# Sheet1.net
KiCad netlist of a schematic drawn in Altium Designer
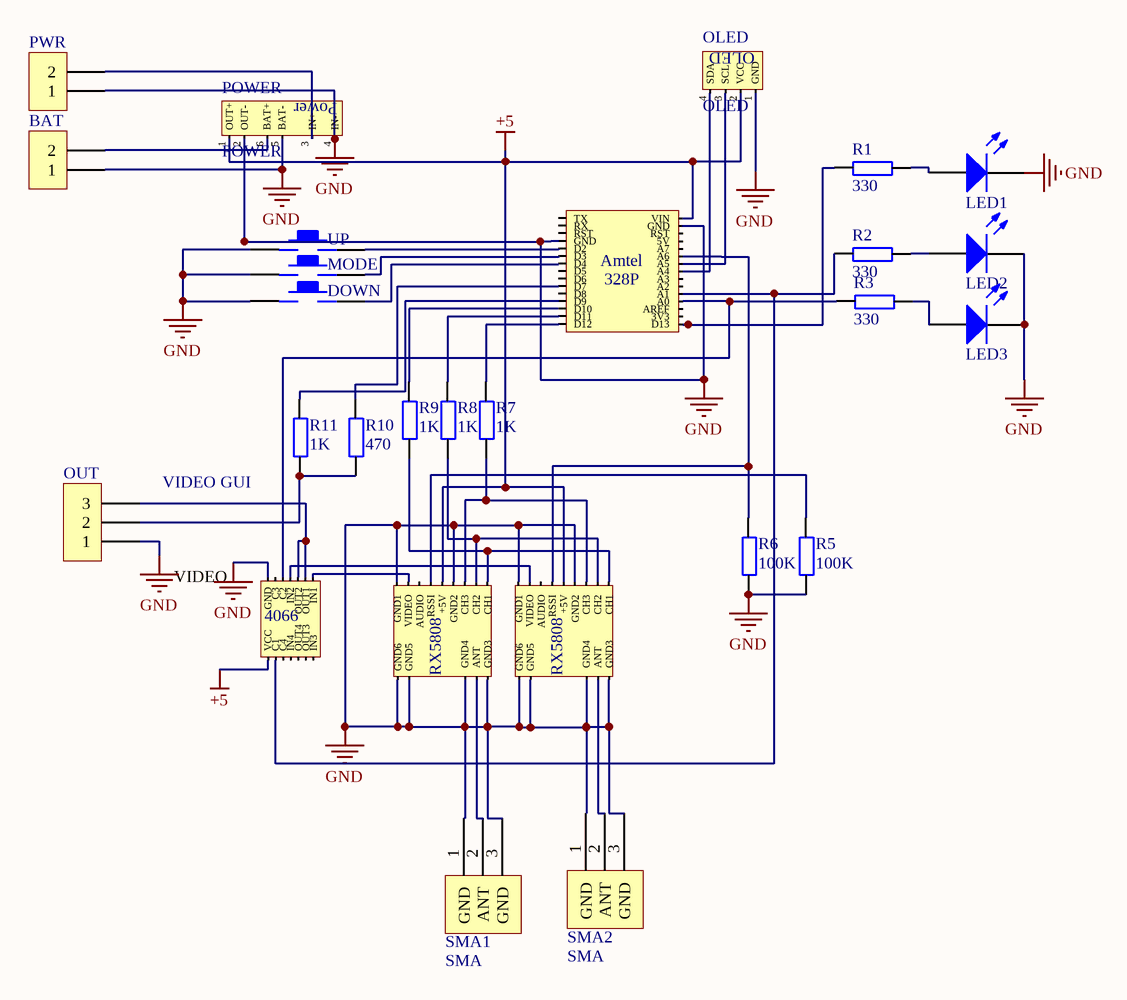
[diagram p0: Sheet1.SchDoc]

(export (version "E")
  (design (tool "Eeschema 10.0.6"))
  (components
    (comp (ref "AT328P") (value "328P") (footprint "328") (libsource (lib "328P") (part "328P")))
    (comp (ref "BAT") (value "CON2") (footprint "SIP2") (libsource (lib "常用元件库") (part "CON2")))
    (comp (ref "CD4066") (value "CD4066") (footprint "4066") (libsource (lib "CD4066") (part "CD4066")))
    (comp (ref "DS1")
      (value "LED1")
      (footprint "1206")
      (description "Typical RED, GREEN, YELLOW, AMBER GaAs LED")
      (fields (field (name "PUBLISHER") "Altium Limited"))
      (libsource (lib "MiniSTM32 V3.0封装库") (part "LED2"))
    )
    (comp (ref "DS2")
      (value "LED2")
      (footprint "1206")
      (description "Typical RED, GREEN, YELLOW, AMBER GaAs LED")
      (fields (field (name "PUBLISHER") "Altium Limited"))
      (libsource (lib "MiniSTM32 V3.0封装库") (part "LED2"))
    )
    (comp (ref "DS3")
      (value "LED3")
      (footprint "1206")
      (description "Typical RED, GREEN, YELLOW, AMBER GaAs LED")
      (fields (field (name "PUBLISHER") "Altium Limited"))
      (libsource (lib "MiniSTM32 V3.0封装库") (part "LED2"))
    )
    (comp (ref "KEY1") (value "UP") (footprint "KEY_M") (libsource (lib "MiniSTM32 V3.0封装库") (part "KEY_M")))
    (comp (ref "KEY2")
      (value "MODE")
      (footprint "KEY_M")
      (libsource (lib "MiniSTM32 V3.0封装库") (part "KEY_M"))
    )
    (comp (ref "KEY3")
      (value "DOWN")
      (footprint "KEY_M")
      (libsource (lib "MiniSTM32 V3.0封装库") (part "KEY_M"))
    )
    (comp (ref "OLED") (value "OLED") (footprint "oled") (libsource (lib "OLED") (part "OLED")))
    (comp (ref "OUT") (value "CON3") (footprint "SIP3") (libsource (lib "常用元件库") (part "CON3")))
    (comp (ref "POWER") (value "POWER") (footprint "power") (libsource (lib "POWER") (part "POWER")))
    (comp (ref "PWR") (value "CON1") (footprint "SIP2") (libsource (lib "常用元件库") (part "CON2")))
    (comp (ref "R1") (value "330") (footprint "0805") (libsource (lib "MiniSTM32 V3.0封装库") (part "R")))
    (comp (ref "R2") (value "330") (footprint "0805") (libsource (lib "MiniSTM32 V3.0封装库") (part "R")))
    (comp (ref "R3") (value "330") (footprint "0805") (libsource (lib "MiniSTM32 V3.0封装库") (part "R")))
    (comp (ref "R5") (value "100K") (footprint "0805") (libsource (lib "MiniSTM32 V3.0封装库") (part "R")))
    (comp (ref "R6") (value "100K") (footprint "0805") (libsource (lib "MiniSTM32 V3.0封装库") (part "R")))
    (comp (ref "R7") (value "1K") (footprint "0805") (libsource (lib "MiniSTM32 V3.0封装库") (part "R")))
    (comp (ref "R8") (value "1K") (footprint "0805") (libsource (lib "MiniSTM32 V3.0封装库") (part "R")))
    (comp (ref "R9") (value "1K") (footprint "0805") (libsource (lib "MiniSTM32 V3.0封装库") (part "R")))
    (comp (ref "R10") (value "470") (footprint "0805") (libsource (lib "MiniSTM32 V3.0封装库") (part "R")))
    (comp (ref "R11") (value "1K") (footprint "0805") (libsource (lib "MiniSTM32 V3.0封装库") (part "R")))
    (comp (ref "RX5808 1") (value "RX5808") (footprint "rx5808") (libsource (lib "RX5808") (part "RX5808")))
    (comp (ref "RX5808 2") (value "RX5808") (footprint "rx5808") (libsource (lib "RX5808") (part "RX5808")))
    (comp (ref "SMA1") (value "SMA") (footprint "SMA") (libsource (lib "SMA") (part "Component_1")))
    (comp (ref "SMA2") (value "SMA") (footprint "SMA") (libsource (lib "SMA") (part "Component_1")))
  )
  (nets
    (net (code "1") (name "+5") (class "Default")
      (node (ref "AT328P") (pin "30") (pinfunction "VIN_30") (pintype "passive"))
      (node (ref "CD4066") (pin "14") (pinfunction "VCC_14") (pintype "passive"))
      (node (ref "OLED") (pin "2") (pinfunction "VCC_2") (pintype "passive"))
      (node (ref "POWER") (pin "1") (pinfunction "OUT+_1") (pintype "passive"))
      (node (ref "RX5808 1") (pin "5") (pinfunction "+5V_5") (pintype "passive"))
      (node (ref "RX5808 2") (pin "5") (pinfunction "+5V_5") (pintype "passive"))
    )
    (net (code "2") (name "GND") (class "Default")
      (node (ref "AT328P") (pin "29") (pinfunction "GND_29") (pintype "passive"))
      (node (ref "AT328P") (pin "4") (pinfunction "GND_4") (pintype "passive"))
      (node (ref "BAT") (pin "1") (pinfunction "1_1") (pintype "passive"))
      (node (ref "CD4066") (pin "7") (pinfunction "GND_7") (pintype "passive"))
      (node (ref "DS1") (pin "2") (pinfunction "K_2") (pintype "passive"))
      (node (ref "DS2") (pin "2") (pinfunction "K_2") (pintype "passive"))
      (node (ref "DS3") (pin "2") (pinfunction "K_2") (pintype "passive"))
      (node (ref "KEY1") (pin "1") (pinfunction "1_1") (pintype "passive"))
      (node (ref "KEY2") (pin "1") (pinfunction "1_1") (pintype "passive"))
      (node (ref "KEY3") (pin "1") (pinfunction "1_1") (pintype "passive"))
      (node (ref "OLED") (pin "1") (pinfunction "GND_1") (pintype "passive"))
      (node (ref "OUT") (pin "1") (pinfunction "1_1") (pintype "passive"))
      (node (ref "POWER") (pin "2") (pinfunction "OUT-_2") (pintype "passive"))
      (node (ref "POWER") (pin "4") (pinfunction "IN-_4") (pintype "passive"))
      (node (ref "POWER") (pin "5") (pinfunction "BAT-_5") (pintype "passive"))
      (node (ref "PWR") (pin "1") (pinfunction "1_1") (pintype "passive"))
      (node (ref "R5") (pin "1") (pintype "passive"))
      (node (ref "R6") (pin "1") (pintype "passive"))
      (node (ref "RX5808 1") (pin "10") (pinfunction "GND3_10") (pintype "passive"))
      (node (ref "RX5808 1") (pin "12") (pinfunction "GND4_12") (pintype "passive"))
      (node (ref "RX5808 1") (pin "13") (pinfunction "GND5_13") (pintype "passive"))
      (node (ref "RX5808 1") (pin "14") (pinfunction "GND6_14") (pintype "passive"))
      (node (ref "RX5808 1") (pin "4") (pinfunction "GND2_4") (pintype "passive"))
      (node (ref "RX5808 1") (pin "9") (pinfunction "GND1_9") (pintype "passive"))
      (node (ref "RX5808 2") (pin "10") (pinfunction "GND3_10") (pintype "passive"))
      (node (ref "RX5808 2") (pin "12") (pinfunction "GND4_12") (pintype "passive"))
      (node (ref "RX5808 2") (pin "13") (pinfunction "GND5_13") (pintype "passive"))
      (node (ref "RX5808 2") (pin "14") (pinfunction "GND6_14") (pintype "passive"))
      (node (ref "RX5808 2") (pin "4") (pinfunction "GND2_4") (pintype "passive"))
      (node (ref "RX5808 2") (pin "9") (pinfunction "GND1_9") (pintype "passive"))
      (node (ref "SMA1") (pin "1") (pinfunction "GND_1") (pintype "passive"))
      (node (ref "SMA1") (pin "3") (pinfunction "GND_3") (pintype "passive"))
      (node (ref "SMA2") (pin "1") (pinfunction "GND_1") (pintype "passive"))
      (node (ref "SMA2") (pin "3") (pinfunction "GND_3") (pintype "passive"))
    )
    (net (code "3") (name "Net-(AT328P-A0)") (class "Default")
      (node (ref "AT328P") (pin "19") (pinfunction "A0_19") (pintype "passive"))
      (node (ref "CD4066") (pin "5") (pinfunction "C2_5") (pintype "passive"))
      (node (ref "R3") (pin "1") (pintype "passive"))
    )
    (net (code "4") (name "Net-(AT328P-A1)") (class "Default")
      (node (ref "AT328P") (pin "20") (pinfunction "A1_20") (pintype "passive"))
      (node (ref "CD4066") (pin "13") (pinfunction "C1_13") (pintype "passive"))
      (node (ref "R2") (pin "1") (pintype "passive"))
    )
    (net (code "5") (name "Net-(AT328P-A4)") (class "Default")
      (node (ref "AT328P") (pin "23") (pinfunction "A4_23") (pintype "passive"))
      (node (ref "OLED") (pin "4") (pinfunction "SDA_4") (pintype "passive"))
    )
    (net (code "6") (name "Net-(AT328P-A5)") (class "Default")
      (node (ref "AT328P") (pin "24") (pinfunction "A5_24") (pintype "passive"))
      (node (ref "OLED") (pin "3") (pinfunction "SCL_3") (pintype "passive"))
    )
    (net (code "7") (name "Net-(AT328P-A6)") (class "Default")
      (node (ref "AT328P") (pin "25") (pinfunction "A6_25") (pintype "passive"))
      (node (ref "R6") (pin "2") (pintype "passive"))
      (node (ref "RX5808 2") (pin "6") (pinfunction "RSSI_6") (pintype "passive"))
    )
    (net (code "8") (name "Net-(AT328P-D2)") (class "Default")
      (node (ref "AT328P") (pin "5") (pinfunction "D2_5") (pintype "passive"))
      (node (ref "KEY1") (pin "2") (pinfunction "2_2") (pintype "passive"))
    )
    (net (code "9") (name "Net-(AT328P-D3)") (class "Default")
      (node (ref "AT328P") (pin "6") (pinfunction "D3_6") (pintype "passive"))
      (node (ref "KEY2") (pin "2") (pinfunction "2_2") (pintype "passive"))
    )
    (net (code "10") (name "Net-(AT328P-D4)") (class "Default")
      (node (ref "AT328P") (pin "7") (pinfunction "D4_7") (pintype "passive"))
      (node (ref "KEY3") (pin "2") (pinfunction "2_2") (pintype "passive"))
    )
    (net (code "11") (name "Net-(AT328P-D7)") (class "Default")
      (node (ref "AT328P") (pin "10") (pinfunction "D7_10") (pintype "passive"))
      (node (ref "R10") (pin "2") (pintype "passive"))
    )
    (net (code "12") (name "Net-(AT328P-D9)") (class "Default")
      (node (ref "AT328P") (pin "12") (pinfunction "D9_12") (pintype "passive"))
      (node (ref "R11") (pin "2") (pintype "passive"))
    )
    (net (code "13") (name "Net-(AT328P-D10)") (class "Default")
      (node (ref "AT328P") (pin "13") (pinfunction "D10_13") (pintype "passive"))
      (node (ref "R9") (pin "2") (pintype "passive"))
    )
    (net (code "14") (name "Net-(AT328P-D11)") (class "Default")
      (node (ref "AT328P") (pin "14") (pinfunction "D11_14") (pintype "passive"))
      (node (ref "R8") (pin "2") (pintype "passive"))
    )
    (net (code "15") (name "Net-(AT328P-D12)") (class "Default")
      (node (ref "AT328P") (pin "15") (pinfunction "D12_15") (pintype "passive"))
      (node (ref "R7") (pin "2") (pintype "passive"))
    )
    (net (code "16") (name "Net-(AT328P-D13)") (class "Default")
      (node (ref "AT328P") (pin "16") (pinfunction "D13_16") (pintype "passive"))
      (node (ref "R1") (pin "1") (pintype "passive"))
    )
    (net (code "17") (name "Net-(CD4066-IN1)") (class "Default")
      (node (ref "CD4066") (pin "1") (pinfunction "IN1_1") (pintype "passive"))
      (node (ref "RX5808 1") (pin "8") (pinfunction "VIDEO_8") (pintype "passive"))
    )
    (net (code "18") (name "Net-(CD4066-IN2)") (class "Default")
      (node (ref "CD4066") (pin "4") (pinfunction "IN2_4") (pintype "passive"))
      (node (ref "RX5808 2") (pin "8") (pinfunction "VIDEO_8") (pintype "passive"))
    )
    (net (code "19") (name "Net-(CD4066-OUT1)") (class "Default")
      (node (ref "CD4066") (pin "2") (pinfunction "OUT1_2") (pintype "passive"))
      (node (ref "CD4066") (pin "3") (pinfunction "OUT2_3") (pintype "passive"))
      (node (ref "OUT") (pin "3") (pinfunction "3_3") (pintype "passive"))
    )
    (net (code "20") (name "Net-(DS1-A)") (class "Default")
      (node (ref "DS1") (pin "1") (pinfunction "A_1") (pintype "passive"))
      (node (ref "R1") (pin "2") (pintype "passive"))
    )
    (net (code "21") (name "Net-(DS2-A)") (class "Default")
      (node (ref "DS2") (pin "1") (pinfunction "A_1") (pintype "passive"))
      (node (ref "R2") (pin "2") (pintype "passive"))
    )
    (net (code "22") (name "Net-(DS3-A)") (class "Default")
      (node (ref "DS3") (pin "1") (pinfunction "A_1") (pintype "passive"))
      (node (ref "R3") (pin "2") (pintype "passive"))
    )
    (net (code "23") (name "Net-(OUT-Pad2)") (class "Default")
      (node (ref "OUT") (pin "2") (pinfunction "2_2") (pintype "passive"))
      (node (ref "R10") (pin "1") (pintype "passive"))
      (node (ref "R11") (pin "1") (pintype "passive"))
    )
    (net (code "24") (name "Net-(POWER-BAT+)") (class "Default")
      (node (ref "BAT") (pin "2") (pinfunction "2_2") (pintype "passive"))
      (node (ref "POWER") (pin "6") (pinfunction "BAT+_6") (pintype "passive"))
    )
    (net (code "25") (name "Net-(POWER-IN+)") (class "Default")
      (node (ref "POWER") (pin "3") (pinfunction "IN+_3") (pintype "passive"))
      (node (ref "PWR") (pin "2") (pinfunction "2_2") (pintype "passive"))
    )
    (net (code "26") (name "Net-(RX5808 1-ANT)") (class "Default")
      (node (ref "RX5808 1") (pin "11") (pinfunction "ANT_11") (pintype "passive"))
      (node (ref "SMA1") (pin "2") (pinfunction "ANT_2") (pintype "passive"))
    )
    (net (code "27") (name "Net-(RX5808 1-CH1)") (class "Default")
      (node (ref "R9") (pin "1") (pintype "passive"))
      (node (ref "RX5808 1") (pin "1") (pinfunction "CH1_1") (pintype "passive"))
      (node (ref "RX5808 2") (pin "1") (pinfunction "CH1_1") (pintype "passive"))
    )
    (net (code "28") (name "Net-(RX5808 1-CH2)") (class "Default")
      (node (ref "R8") (pin "1") (pintype "passive"))
      (node (ref "RX5808 1") (pin "2") (pinfunction "CH2_2") (pintype "passive"))
      (node (ref "RX5808 2") (pin "2") (pinfunction "CH2_2") (pintype "passive"))
    )
    (net (code "29") (name "Net-(RX5808 1-CH3)") (class "Default")
      (node (ref "R7") (pin "1") (pintype "passive"))
      (node (ref "RX5808 1") (pin "3") (pinfunction "CH3_3") (pintype "passive"))
      (node (ref "RX5808 2") (pin "3") (pinfunction "CH3_3") (pintype "passive"))
    )
    (net (code "30") (name "Net-(RX5808 1-RSSI)") (class "Default")
      (node (ref "R5") (pin "2") (pintype "passive"))
      (node (ref "RX5808 1") (pin "6") (pinfunction "RSSI_6") (pintype "passive"))
    )
    (net (code "31") (name "Net-(RX5808 2-ANT)") (class "Default")
      (node (ref "RX5808 2") (pin "11") (pinfunction "ANT_11") (pintype "passive"))
      (node (ref "SMA2") (pin "2") (pinfunction "ANT_2") (pintype "passive"))
    )
    (net (code "32") (name "unconnected-(AT328P-3V3-Pad17)") (class "Default")
      (node (ref "AT328P") (pin "17") (pinfunction "3V3_17") (pintype "passive"))
    )
    (net (code "33") (name "unconnected-(AT328P-5V-Pad27)") (class "Default")
      (node (ref "AT328P") (pin "27") (pinfunction "5V_27") (pintype "passive"))
    )
    (net (code "34") (name "unconnected-(AT328P-A2-Pad21)") (class "Default")
      (node (ref "AT328P") (pin "21") (pinfunction "A2_21") (pintype "passive"))
    )
    (net (code "35") (name "unconnected-(AT328P-A3-Pad22)") (class "Default")
      (node (ref "AT328P") (pin "22") (pinfunction "A3_22") (pintype "passive"))
    )
    (net (code "36") (name "unconnected-(AT328P-A7-Pad26)") (class "Default")
      (node (ref "AT328P") (pin "26") (pinfunction "A7_26") (pintype "passive"))
    )
    (net (code "37") (name "unconnected-(AT328P-AREF-Pad18)") (class "Default")
      (node (ref "AT328P") (pin "18") (pinfunction "AREF_18") (pintype "passive"))
    )
    (net (code "38") (name "unconnected-(AT328P-D5-Pad8)") (class "Default")
      (node (ref "AT328P") (pin "8") (pinfunction "D5_8") (pintype "passive"))
    )
    (net (code "39") (name "unconnected-(AT328P-D6-Pad9)") (class "Default")
      (node (ref "AT328P") (pin "9") (pinfunction "D6_9") (pintype "passive"))
    )
    (net (code "40") (name "unconnected-(AT328P-D8-Pad11)") (class "Default")
      (node (ref "AT328P") (pin "11") (pinfunction "D8_11") (pintype "passive"))
    )
    (net (code "41") (name "unconnected-(AT328P-RST-Pad3)") (class "Default")
      (node (ref "AT328P") (pin "3") (pinfunction "RST_3") (pintype "passive"))
    )
    (net (code "42") (name "unconnected-(AT328P-RST-Pad28)") (class "Default")
      (node (ref "AT328P") (pin "28") (pinfunction "RST_28") (pintype "passive"))
    )
    (net (code "43") (name "unconnected-(AT328P-RX-Pad2)") (class "Default")
      (node (ref "AT328P") (pin "2") (pinfunction "RX_2") (pintype "passive"))
    )
    (net (code "44") (name "unconnected-(AT328P-TX-Pad1)") (class "Default")
      (node (ref "AT328P") (pin "1") (pinfunction "TX_1") (pintype "passive"))
    )
    (net (code "45") (name "unconnected-(CD4066-C3-Pad6)") (class "Default")
      (node (ref "CD4066") (pin "6") (pinfunction "C3_6") (pintype "passive"))
    )
    (net (code "46") (name "unconnected-(CD4066-C4-Pad12)") (class "Default")
      (node (ref "CD4066") (pin "12") (pinfunction "C4_12") (pintype "passive"))
    )
    (net (code "47") (name "unconnected-(CD4066-IN3-Pad8)") (class "Default")
      (node (ref "CD4066") (pin "8") (pinfunction "IN3_8") (pintype "passive"))
    )
    (net (code "48") (name "unconnected-(CD4066-IN4-Pad11)") (class "Default")
      (node (ref "CD4066") (pin "11") (pinfunction "IN4_11") (pintype "passive"))
    )
    (net (code "49") (name "unconnected-(CD4066-OUT3-Pad9)") (class "Default")
      (node (ref "CD4066") (pin "9") (pinfunction "OUT3_9") (pintype "passive"))
    )
    (net (code "50") (name "unconnected-(CD4066-OUT4-Pad10)") (class "Default")
      (node (ref "CD4066") (pin "10") (pinfunction "OUT4_10") (pintype "passive"))
    )
    (net (code "51") (name "unconnected-(RX5808 1-AUDIO-Pad7)") (class "Default")
      (node (ref "RX5808 1") (pin "7") (pinfunction "AUDIO_7") (pintype "passive"))
    )
    (net (code "52") (name "unconnected-(RX5808 2-AUDIO-Pad7)") (class "Default")
      (node (ref "RX5808 2") (pin "7") (pinfunction "AUDIO_7") (pintype "passive"))
    )
  )
)
